# piezo-jfet-buffer-simple-2x_v2.net
KiCad netlist of a schematic drawn in EAGLE
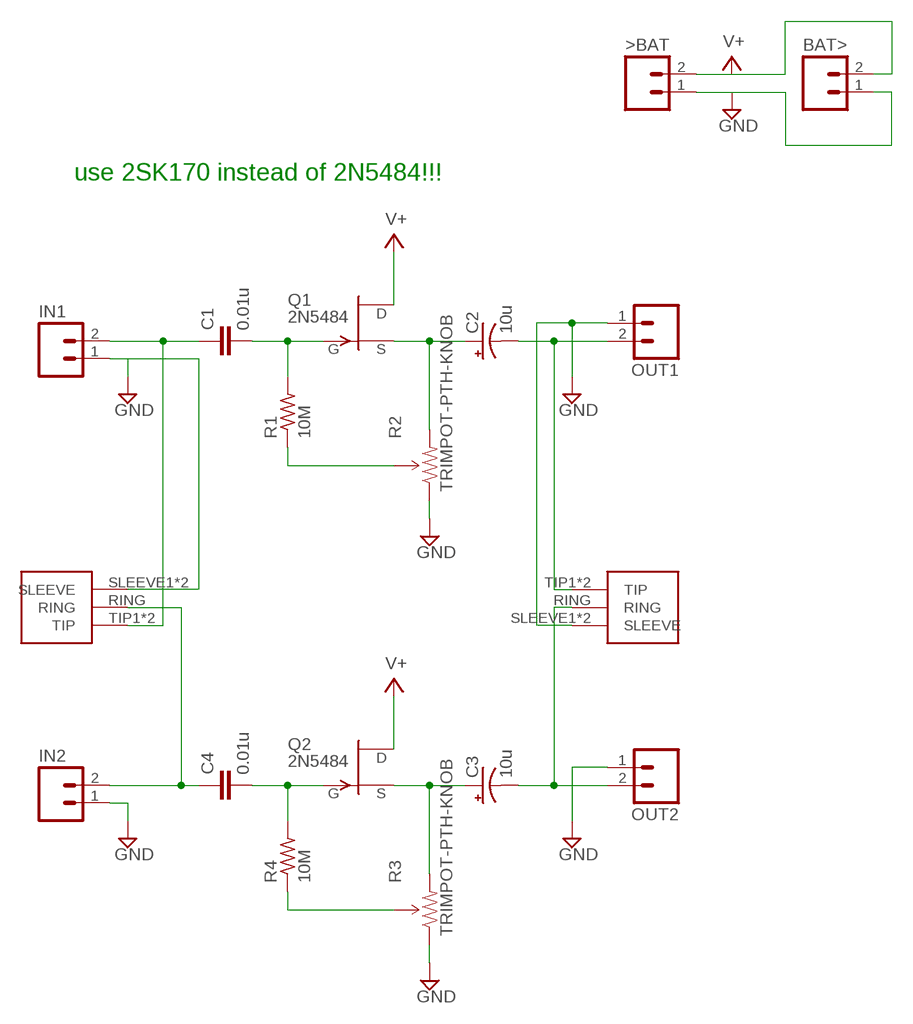
[diagram p0: schematic, sheet 1]

(export (version "E")
  (design (tool "Eeschema 10.0.6"))
  (components
    (comp (ref ">BAT")
      (value "M02PTH")
      (footprint "eagle-import:1X02")
      (libsource (lib "eagle-import") (part "M02PTH"))
    )
    (comp (ref "BAT>")
      (value "M02PTH")
      (footprint "eagle-import:1X02")
      (libsource (lib "eagle-import") (part "M02PTH"))
    )
    (comp (ref "C1")
      (value "0.01u")
      (footprint "eagle-import:C5B3")
      (libsource (lib "eagle-import") (part "C5/3"))
    )
    (comp (ref "C2")
      (value "10u")
      (footprint "eagle-import:CPOL-RADIAL-10UF-25V")
      (libsource (lib "eagle-import") (part "CAP_POLPTH2"))
    )
    (comp (ref "C3")
      (value "10u")
      (footprint "eagle-import:CPOL-RADIAL-10UF-25V")
      (libsource (lib "eagle-import") (part "CAP_POLPTH2"))
    )
    (comp (ref "C4")
      (value "0.01u")
      (footprint "eagle-import:C5B3")
      (libsource (lib "eagle-import") (part "C5/3"))
    )
    (comp (ref "IN1")
      (value "M02LOCK")
      (footprint "eagle-import:1X02_LOCK")
      (libsource (lib "eagle-import") (part "M02LOCK"))
    )
    (comp (ref "IN2")
      (value "M02LOCK")
      (footprint "eagle-import:1X02_LOCK")
      (libsource (lib "eagle-import") (part "M02LOCK"))
    )
    (comp (ref "OUT1")
      (value "M02LOCK")
      (footprint "eagle-import:1X02_LOCK")
      (libsource (lib "eagle-import") (part "M02LOCK"))
    )
    (comp (ref "OUT2")
      (value "M02LOCK")
      (footprint "eagle-import:1X02_LOCK")
      (libsource (lib "eagle-import") (part "M02LOCK"))
    )
    (comp (ref "Q1")
      (value "2N5484")
      (footprint "eagle-import:TO92-")
      (libsource (lib "eagle-import") (part "?5482N4"))
    )
    (comp (ref "Q2")
      (value "2N5484")
      (footprint "eagle-import:TO92-")
      (libsource (lib "eagle-import") (part "?5482N4"))
    )
    (comp (ref "R1")
      (value "10M")
      (footprint "eagle-import:0204V")
      (libsource (lib "eagle-import") (part "R-US_0204/2V"))
    )
    (comp (ref "R2")
      (value "TRIMPOT-PTH-KNOB")
      (footprint "eagle-import:3386U")
      (libsource (lib "eagle-import") (part "TRIMPOT-PTH-KNOB"))
    )
    (comp (ref "R3")
      (value "TRIMPOT-PTH-KNOB")
      (footprint "eagle-import:3386U")
      (libsource (lib "eagle-import") (part "TRIMPOT-PTH-KNOB"))
    )
    (comp (ref "R4")
      (value "10M")
      (footprint "eagle-import:0204V")
      (libsource (lib "eagle-import") (part "R-US_0204/2V"))
    )
    (comp (ref "U$1")
      (value "1/8\"-F-STEREO-PCB")
      (footprint "eagle-import:1_8_-F-STEREO-PCB")
      (libsource (lib "eagle-import") (part "1/8{dblquote}-F-STEREO-PCB"))
    )
    (comp (ref "U$2")
      (value "1/8\"-F-STEREO-PCB")
      (footprint "eagle-import:1_8_-F-STEREO-PCB")
      (libsource (lib "eagle-import") (part "1/8{dblquote}-F-STEREO-PCB"))
    )
  )
  (nets
    (net (code "1") (name "GND") (class "Default")
      (node (ref ">BAT") (pin "1") (pinfunction "1_1") (pintype "passive"))
      (node (ref "BAT>") (pin "1") (pinfunction "1_1") (pintype "passive"))
      (node (ref "IN1") (pin "1") (pinfunction "1_1") (pintype "passive"))
      (node (ref "IN2") (pin "1") (pinfunction "1_1") (pintype "passive"))
      (node (ref "OUT1") (pin "1") (pinfunction "1_1") (pintype "passive"))
      (node (ref "OUT2") (pin "1") (pinfunction "1_1") (pintype "passive"))
      (node (ref "R2") (pin "1") (pinfunction "CCW_1") (pintype "passive"))
      (node (ref "R3") (pin "1") (pinfunction "CCW_1") (pintype "passive"))
      (node (ref "U$1") (pin "SLEEVE1") (pinfunction "SLEEVE_SLEEVE1") (pintype "bidirectional"))
      (node (ref "U$1") (pin "SLEEVE2") (pinfunction "SLEEVE_SLEEVE2") (pintype "bidirectional"))
      (node (ref "U$2") (pin "SLEEVE1") (pinfunction "SLEEVE_SLEEVE1") (pintype "bidirectional"))
      (node (ref "U$2") (pin "SLEEVE2") (pinfunction "SLEEVE_SLEEVE2") (pintype "bidirectional"))
    )
    (net (code "2") (name "Net-(C1-Pad1)") (class "Default")
      (node (ref "C1") (pin "1") (pinfunction "1_1") (pintype "passive"))
      (node (ref "IN1") (pin "2") (pinfunction "2_2") (pintype "passive"))
      (node (ref "U$2") (pin "TIP1") (pinfunction "TIP_TIP1") (pintype "bidirectional"))
      (node (ref "U$2") (pin "TIP2") (pinfunction "TIP_TIP2") (pintype "bidirectional"))
    )
    (net (code "3") (name "Net-(C2-+)") (class "Default")
      (node (ref "C2") (pin "1") (pinfunction "+_1") (pintype "passive"))
      (node (ref "Q1") (pin "2") (pinfunction "S_2") (pintype "passive"))
      (node (ref "R2") (pin "3") (pinfunction "CW_3") (pintype "passive"))
    )
    (net (code "4") (name "Net-(C2--)") (class "Default")
      (node (ref "C2") (pin "2") (pinfunction "-_2") (pintype "passive"))
      (node (ref "OUT1") (pin "2") (pinfunction "2_2") (pintype "passive"))
      (node (ref "U$1") (pin "TIP1") (pinfunction "TIP_TIP1") (pintype "bidirectional"))
      (node (ref "U$1") (pin "TIP2") (pinfunction "TIP_TIP2") (pintype "bidirectional"))
    )
    (net (code "5") (name "Net-(C3-+)") (class "Default")
      (node (ref "C3") (pin "1") (pinfunction "+_1") (pintype "passive"))
      (node (ref "Q2") (pin "2") (pinfunction "S_2") (pintype "passive"))
      (node (ref "R3") (pin "3") (pinfunction "CW_3") (pintype "passive"))
    )
    (net (code "6") (name "Net-(C3--)") (class "Default")
      (node (ref "C3") (pin "2") (pinfunction "-_2") (pintype "passive"))
      (node (ref "OUT2") (pin "2") (pinfunction "2_2") (pintype "passive"))
      (node (ref "U$1") (pin "RING") (pinfunction "RING_RING") (pintype "bidirectional"))
    )
    (net (code "7") (name "Net-(C4-Pad1)") (class "Default")
      (node (ref "C4") (pin "1") (pinfunction "1_1") (pintype "passive"))
      (node (ref "IN2") (pin "2") (pinfunction "2_2") (pintype "passive"))
      (node (ref "U$2") (pin "RING") (pinfunction "RING_RING") (pintype "bidirectional"))
    )
    (net (code "8") (name "Net-(Q1-G)") (class "Default")
      (node (ref "C1") (pin "2") (pinfunction "2_2") (pintype "passive"))
      (node (ref "Q1") (pin "1") (pinfunction "G_1") (pintype "passive"))
      (node (ref "R1") (pin "2") (pinfunction "2_2") (pintype "passive"))
    )
    (net (code "9") (name "Net-(Q2-G)") (class "Default")
      (node (ref "C4") (pin "2") (pinfunction "2_2") (pintype "passive"))
      (node (ref "Q2") (pin "1") (pinfunction "G_1") (pintype "passive"))
      (node (ref "R4") (pin "2") (pinfunction "2_2") (pintype "passive"))
    )
    (net (code "10") (name "Net-(R2-WIPER)") (class "Default")
      (node (ref "R1") (pin "1") (pinfunction "1_1") (pintype "passive"))
      (node (ref "R2") (pin "2") (pinfunction "WIPER_2") (pintype "passive"))
    )
    (net (code "11") (name "Net-(R3-WIPER)") (class "Default")
      (node (ref "R3") (pin "2") (pinfunction "WIPER_2") (pintype "passive"))
      (node (ref "R4") (pin "1") (pinfunction "1_1") (pintype "passive"))
    )
    (net (code "12") (name "V+") (class "Default")
      (node (ref ">BAT") (pin "2") (pinfunction "2_2") (pintype "passive"))
      (node (ref "BAT>") (pin "2") (pinfunction "2_2") (pintype "passive"))
      (node (ref "Q1") (pin "3") (pinfunction "D_3") (pintype "passive"))
      (node (ref "Q2") (pin "3") (pinfunction "D_3") (pintype "passive"))
    )
  )
)
